# Sheet3.net
KiCad netlist of a schematic drawn in Altium Designer
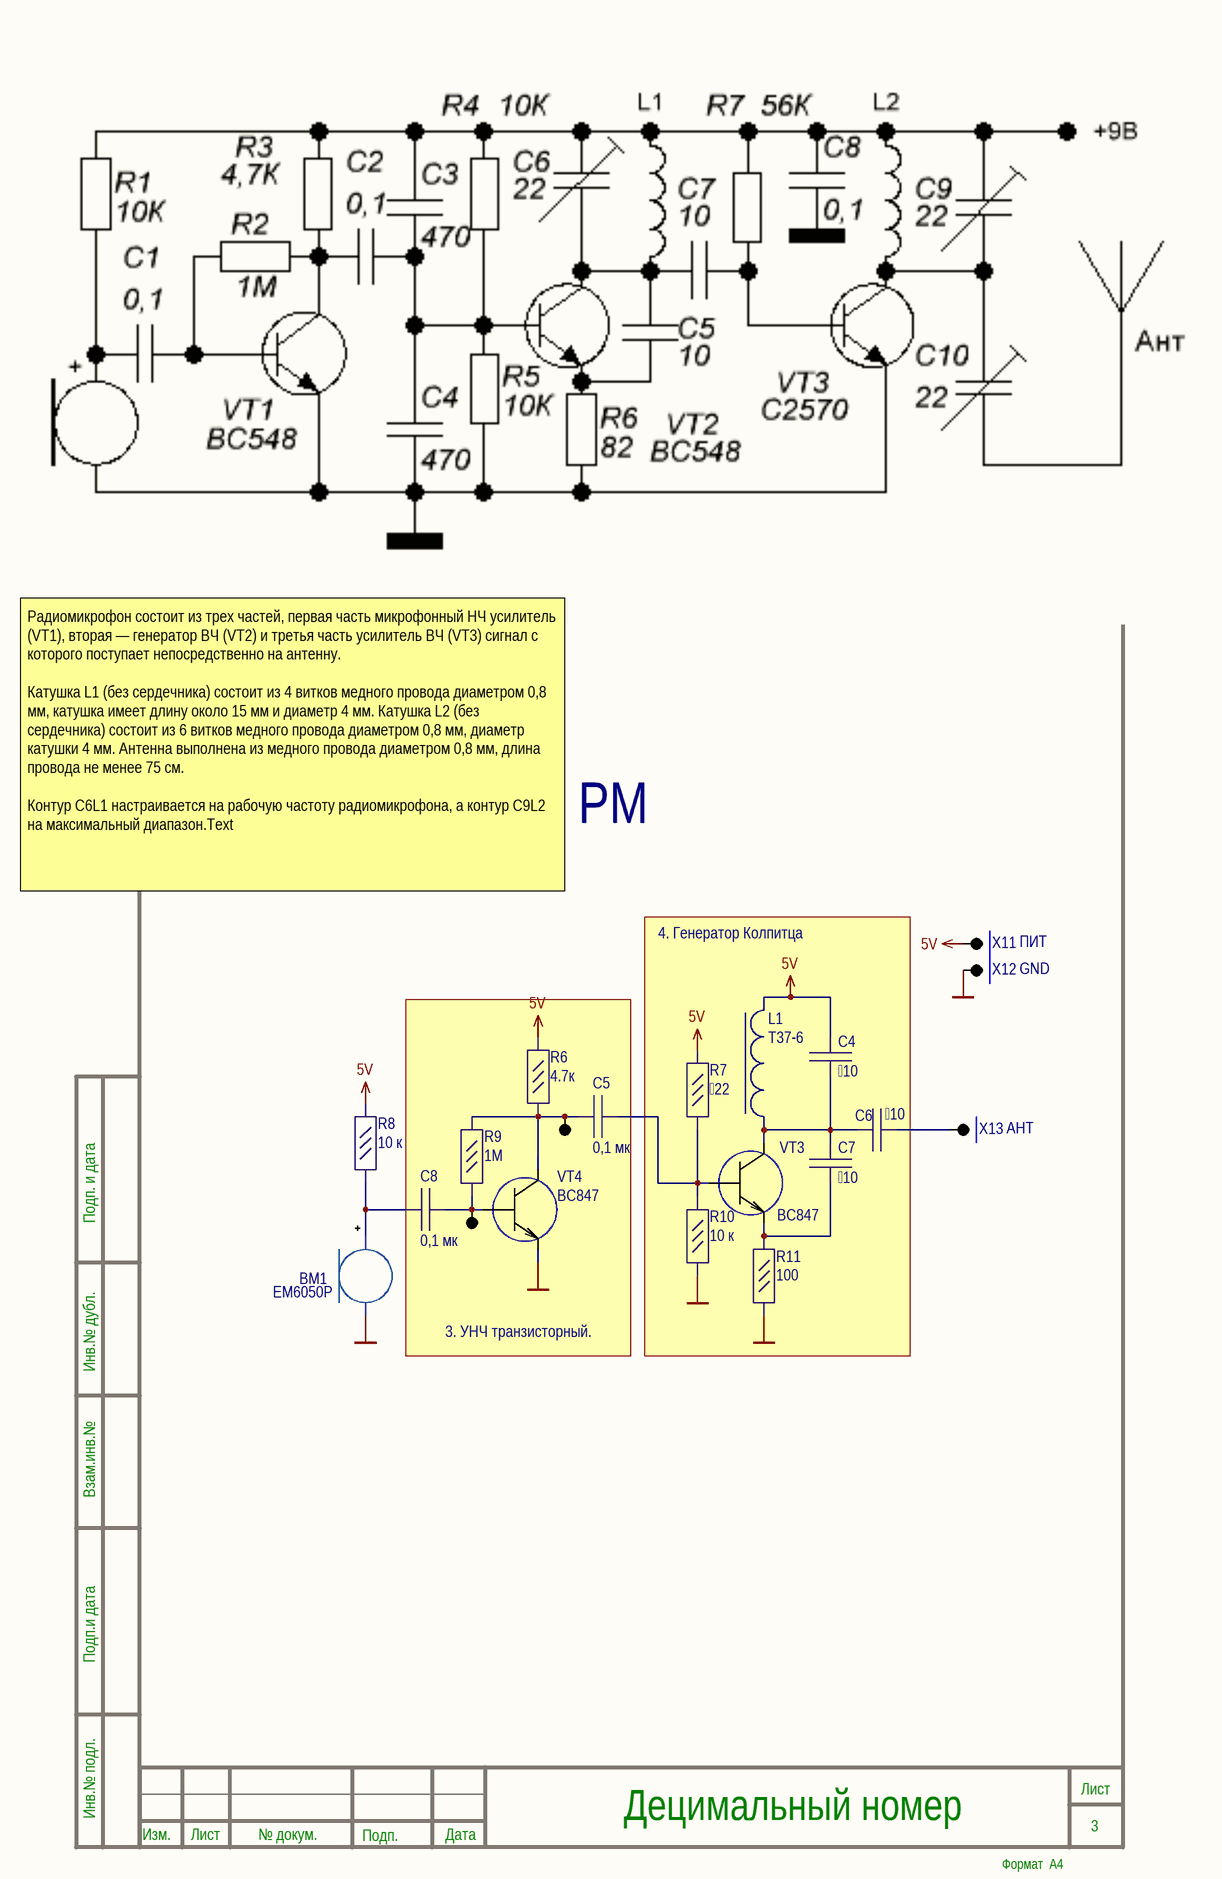
[diagram p0: Sheet3.SchDoc]

(export (version "E")
  (design (tool "Eeschema 10.0.6"))
  (components
    (comp (ref "BM1") (value "EM6050P") (footprint "EM6050P") (libsource (lib "11.Other") (part "EM6050P")))
    (comp (ref "C4")
      (value "10")
      (footprint "C_0603")
      (description "CAP CER 0.1UF 100V X7R 0603")
      (fields
        (field (name "PART NUMBER") "GRM188R72A104KA35D")
        (field (name "MANUFACTURER") "Murata Electronics")
      )
      (libsource (lib "Database_Lib") (part "Capasitor"))
    )
    (comp (ref "C5")
      (value "0,1 мк")
      (footprint "C_0603")
      (description "CAP CER 0.1UF 100V X7R 0603")
      (fields
        (field (name "PART NUMBER") "GRM188R72A104KA35D")
        (field (name "MANUFACTURER") "Murata Electronics")
      )
      (libsource (lib "Database_Lib") (part "Capasitor"))
    )
    (comp (ref "C6")
      (value "10")
      (footprint "C_0603")
      (description "CAP CER 0.1UF 100V X7R 0603")
      (fields
        (field (name "PART NUMBER") "GRM188R72A104KA35D")
        (field (name "MANUFACTURER") "Murata Electronics")
      )
      (libsource (lib "Database_Lib") (part "Capasitor"))
    )
    (comp (ref "C7")
      (value "10")
      (footprint "C_0603")
      (description "CAP CER 0.1UF 100V X7R 0603")
      (fields
        (field (name "PART NUMBER") "GRM188R72A104KA35D")
        (field (name "MANUFACTURER") "Murata Electronics")
      )
      (libsource (lib "Database_Lib") (part "Capasitor"))
    )
    (comp (ref "C8")
      (value "0,1 мк")
      (footprint "C_0603")
      (description "CAP CER 0.1UF 100V X7R 0603")
      (fields
        (field (name "PART NUMBER") "GRM188R72A104KA35D")
        (field (name "MANUFACTURER") "Murata Electronics")
      )
      (libsource (lib "Database_Lib") (part "Capasitor"))
    )
    (comp (ref "L1") (value "T37-6") (footprint "t37") (libsource (lib "3.Inductors") (part "T37-6")))
    (comp (ref "R6")
      (value "4.7к")
      (footprint "R_0603")
      (description "RES SMD 10K OHM 1% 1/10W 0603")
      (fields (field (name "PART NUMBER") "CR0603-FX-1002ELF") (field (name "MANUFACTURER") "Bourns Inc."))
      (libsource (lib "Database_Lib") (part "Resistor"))
    )
    (comp (ref "R7")
      (value "22")
      (footprint "R_0603")
      (description "RES SMD 10K OHM 1% 1/10W 0603")
      (fields (field (name "PART NUMBER") "CR0603-FX-1002ELF") (field (name "MANUFACTURER") "Bourns Inc."))
      (libsource (lib "Database_Lib") (part "Resistor"))
    )
    (comp (ref "R8")
      (value "10 к")
      (footprint "R_0603")
      (description "RES SMD 10K OHM 1% 1/10W 0603")
      (fields (field (name "PART NUMBER") "CR0603-FX-1002ELF") (field (name "MANUFACTURER") "Bourns Inc."))
      (libsource (lib "Database_Lib") (part "Resistor"))
    )
    (comp (ref "R9")
      (value "1М")
      (footprint "R_0603")
      (description "RES SMD 10K OHM 1% 1/10W 0603")
      (fields (field (name "PART NUMBER") "CR0603-FX-1002ELF") (field (name "MANUFACTURER") "Bourns Inc."))
      (libsource (lib "Database_Lib") (part "Resistor"))
    )
    (comp (ref "R10")
      (value "10 к")
      (footprint "R_0603")
      (description "RES SMD 10K OHM 1% 1/10W 0603")
      (fields (field (name "PART NUMBER") "CR0603-FX-1002ELF") (field (name "MANUFACTURER") "Bourns Inc."))
      (libsource (lib "Database_Lib") (part "Resistor"))
    )
    (comp (ref "R11")
      (value "100")
      (footprint "R_0603")
      (description "RES SMD 10K OHM 1% 1/10W 0603")
      (fields (field (name "PART NUMBER") "CR0603-FX-1002ELF") (field (name "MANUFACTURER") "Bourns Inc."))
      (libsource (lib "Database_Lib") (part "Resistor"))
    )
    (comp (ref "TP4")
      (value "Test_Point_1")
      (footprint "Test_point")
      (libsource (lib "7.Connectors") (part "Test_Point_1"))
    )
    (comp (ref "TP5")
      (value "Test_Point_1")
      (footprint "Test_point")
      (libsource (lib "7.Connectors") (part "Test_Point_1"))
    )
    (comp (ref "VT3") (value "BC847") (footprint "SOT23") (libsource (lib "5.Transistors") (part "BC847")))
    (comp (ref "VT4") (value "BC847") (footprint "SOT23") (libsource (lib "5.Transistors") (part "BC847")))
    (comp (ref "X11") (value "КТ") (footprint "KT") (libsource (lib "7.Connectors") (part "КТ")))
    (comp (ref "X12") (value "КТ") (footprint "KT") (libsource (lib "7.Connectors") (part "КТ")))
    (comp (ref "X13") (value "КТ") (footprint "KT") (libsource (lib "7.Connectors") (part "КТ")))
  )
  (nets
    (net (code "1") (name "5V") (class "Default")
      (node (ref "C4") (pin "1") (pinfunction "1_1") (pintype "passive"))
      (node (ref "L1") (pin "2") (pinfunction "2_2") (pintype "passive"))
      (node (ref "R6") (pin "1") (pinfunction "1_1") (pintype "passive"))
      (node (ref "R7") (pin "1") (pinfunction "1_1") (pintype "passive"))
      (node (ref "R8") (pin "1") (pinfunction "1_1") (pintype "passive"))
      (node (ref "X11") (pin "1") (pinfunction "1_1") (pintype "passive"))
    )
    (net (code "2") (name "GND") (class "Default")
      (node (ref "BM1") (pin "2") (pinfunction "2_2") (pintype "passive"))
      (node (ref "R10") (pin "2") (pinfunction "2_2") (pintype "passive"))
      (node (ref "R11") (pin "2") (pinfunction "2_2") (pintype "passive"))
      (node (ref "VT4") (pin "2") (pinfunction "E_2") (pintype "passive"))
      (node (ref "X12") (pin "1") (pinfunction "1_1") (pintype "passive"))
    )
    (net (code "3") (name "Net-(BM1-Pad1)") (class "Default")
      (node (ref "BM1") (pin "1") (pinfunction "1_1") (pintype "passive"))
      (node (ref "C8") (pin "1") (pinfunction "1_1") (pintype "passive"))
      (node (ref "R8") (pin "2") (pinfunction "2_2") (pintype "passive"))
    )
    (net (code "4") (name "Net-(C6-Pad1)") (class "Default")
      (node (ref "C6") (pin "1") (pinfunction "1_1") (pintype "passive"))
      (node (ref "X13") (pin "1") (pinfunction "1_1") (pintype "passive"))
    )
    (net (code "5") (name "Net-(VT3-B)") (class "Default")
      (node (ref "C5") (pin "2") (pinfunction "2_2") (pintype "passive"))
      (node (ref "R10") (pin "1") (pinfunction "1_1") (pintype "passive"))
      (node (ref "R7") (pin "2") (pinfunction "2_2") (pintype "passive"))
      (node (ref "VT3") (pin "1") (pinfunction "B_1") (pintype "passive"))
    )
    (net (code "6") (name "Net-(VT3-C)") (class "Default")
      (node (ref "C4") (pin "2") (pinfunction "2_2") (pintype "passive"))
      (node (ref "C6") (pin "2") (pinfunction "2_2") (pintype "passive"))
      (node (ref "C7") (pin "1") (pinfunction "1_1") (pintype "passive"))
      (node (ref "L1") (pin "1") (pinfunction "1_1") (pintype "passive"))
      (node (ref "VT3") (pin "3") (pinfunction "C_3") (pintype "passive"))
    )
    (net (code "7") (name "Net-(VT3-E)") (class "Default")
      (node (ref "C7") (pin "2") (pinfunction "2_2") (pintype "passive"))
      (node (ref "R11") (pin "1") (pinfunction "1_1") (pintype "passive"))
      (node (ref "VT3") (pin "2") (pinfunction "E_2") (pintype "passive"))
    )
    (net (code "8") (name "Net-(VT4-B)") (class "Default")
      (node (ref "C8") (pin "2") (pinfunction "2_2") (pintype "passive"))
      (node (ref "R9") (pin "2") (pinfunction "2_2") (pintype "passive"))
      (node (ref "TP5") (pin "1") (pinfunction "1_1") (pintype "passive"))
      (node (ref "VT4") (pin "1") (pinfunction "B_1") (pintype "passive"))
    )
    (net (code "9") (name "Net-(VT4-C)") (class "Default")
      (node (ref "C5") (pin "1") (pinfunction "1_1") (pintype "passive"))
      (node (ref "R6") (pin "2") (pinfunction "2_2") (pintype "passive"))
      (node (ref "R9") (pin "1") (pinfunction "1_1") (pintype "passive"))
      (node (ref "TP4") (pin "1") (pinfunction "1_1") (pintype "passive"))
      (node (ref "VT4") (pin "3") (pinfunction "C_3") (pintype "passive"))
    )
  )
)
